# Breakout_Connector.net
KiCad netlist of a schematic drawn in Altium Designer
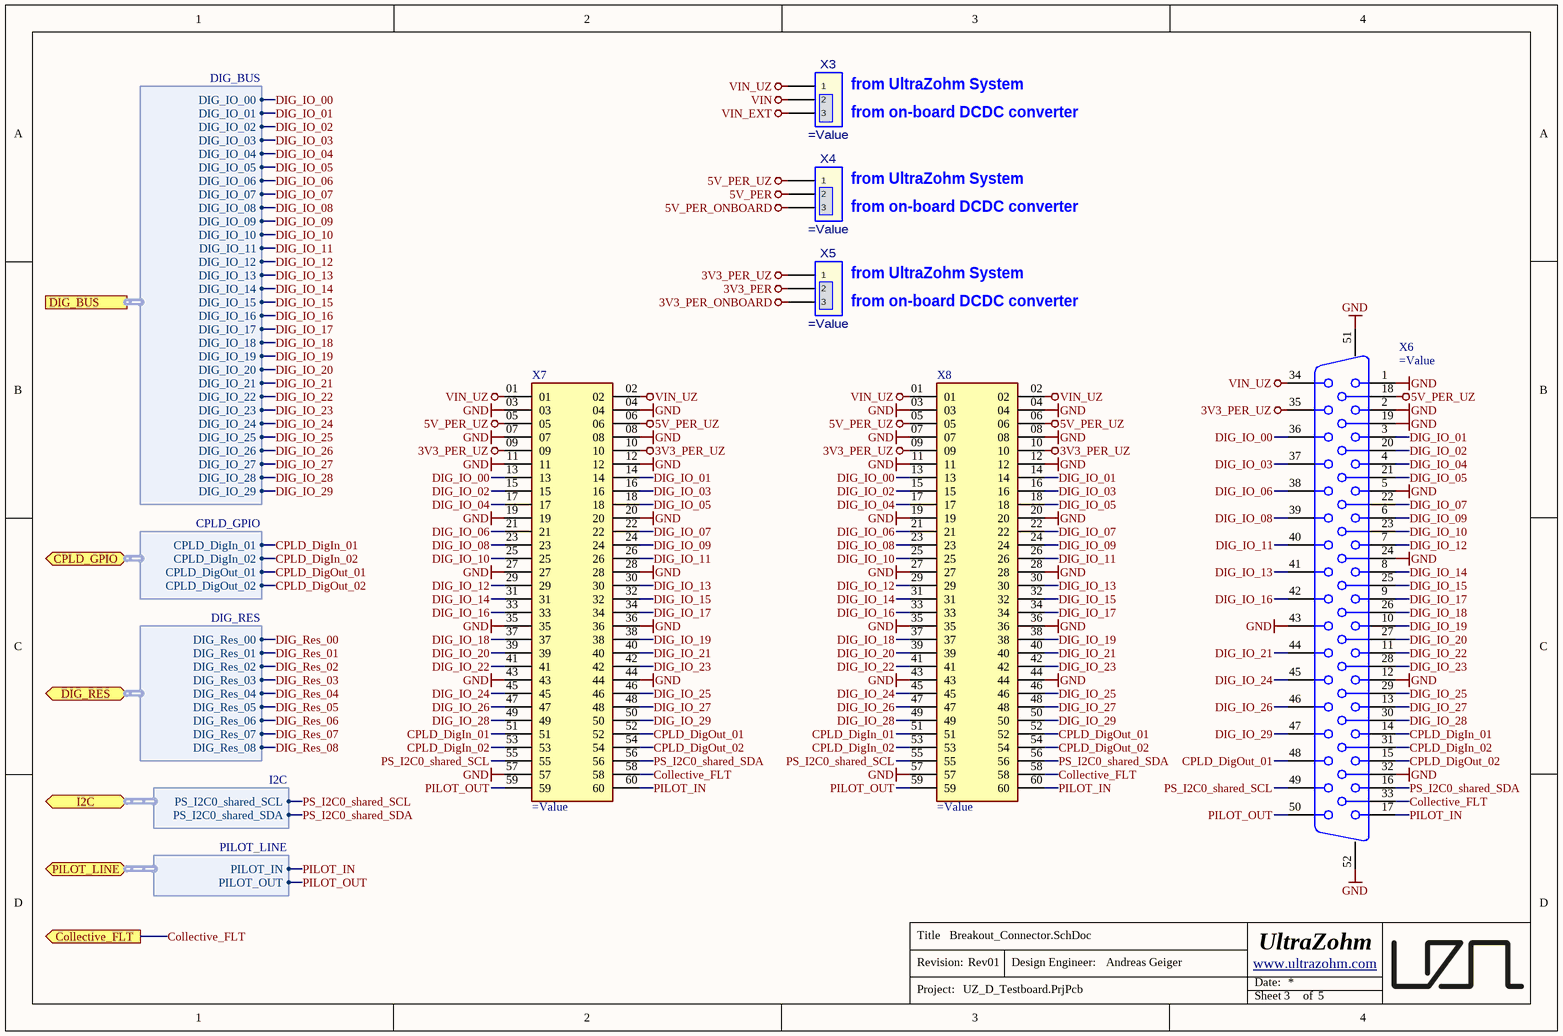
[diagram p0: Breakout_Connector.SchDoc]

(export (version "E")
  (design (tool "Eeschema 10.0.6"))
  (components
    (comp (ref "X3")
      (value "~")
      (footprint "TSW-103-XX-XXX-S")
      (description ".025[0.64] SQ. POST TERMINAL STRIP ASSEMBLY.")
      (fields
        (field (name "MANUFACTURER") "SAMTEC")
        (field (name "MPN") "TSW-103-07-F-S")
        (field (name "CREATED") "2020_11_26_AGeiger")
      )
      (libsource (lib "UZ_D_Testboard") (part "TSW-103-XX-XXX-S"))
    )
    (comp (ref "X4")
      (value "~")
      (footprint "TSW-103-XX-XXX-S")
      (description ".025[0.64] SQ. POST TERMINAL STRIP ASSEMBLY.")
      (fields
        (field (name "MANUFACTURER") "SAMTEC")
        (field (name "MPN") "TSW-103-07-F-S")
        (field (name "CREATED") "2020_11_26_AGeiger")
      )
      (libsource (lib "UZ_D_Testboard") (part "TSW-103-XX-XXX-S"))
    )
    (comp (ref "X5")
      (value "~")
      (footprint "TSW-103-XX-XXX-S")
      (description ".025[0.64] SQ. POST TERMINAL STRIP ASSEMBLY.")
      (fields
        (field (name "MANUFACTURER") "SAMTEC")
        (field (name "MPN") "TSW-103-07-F-S")
        (field (name "CREATED") "2020_11_26_AGeiger")
      )
      (libsource (lib "UZ_D_Testboard") (part "TSW-103-XX-XXX-S"))
    )
    (comp (ref "X6")
      (value "~")
      (footprint "dsub50_male_163A18339X")
      (description "D-SUB, male, right angle, 50pos, 9.4mm pitch")
      (fields
        (field (name "MF") "CONEC")
        (field (name "MPN") "163A18339X")
        (field (name "CREATED") "2021_03_25_AGeiger")
      )
      (libsource (lib "UZ_D_Testboard") (part "DSUB50_male"))
    )
    (comp (ref "X7")
      (value "~")
      (footprint "TSM-130-01-F-DV")
      (fields
        (field (name "MF") "Samtec")
        (field (name "MPN") "TSM-130-01-F-DV")
        (field (name "CREATED") "2021_03_23_AGeiger")
      )
      (libsource (lib "UZ_D_Testboard") (part "TSM-130-01-F-DV"))
    )
    (comp (ref "X8")
      (value "~")
      (footprint "HTSS-130-01-L-DV")
      (fields (field (name "MF") "SAMTEC") (field (name "MPN") "HTSS-130-01-L-DV"))
      (libsource (lib "UZ_D_Testboard") (part "HTSS-130-01-L-DV"))
    )
  )
  (nets
    (net (code "6") (name "/CPLD_DigIn_01") (class "Default")
      (node (ref "X6") (pin "14") (pinfunction "14_14") (pintype "passive"))
      (node (ref "X7") (pin "51") (pinfunction "51_51") (pintype "passive"))
      (node (ref "X8") (pin "51") (pinfunction "51_51") (pintype "passive"))
    )
    (net (code "7") (name "/CPLD_DigIn_02") (class "Default")
      (node (ref "X6") (pin "31") (pinfunction "31_31") (pintype "passive"))
      (node (ref "X7") (pin "53") (pinfunction "53_53") (pintype "passive"))
      (node (ref "X8") (pin "53") (pinfunction "53_53") (pintype "passive"))
    )
    (net (code "8") (name "/CPLD_DigOut_01") (class "Default")
      (node (ref "X6") (pin "48") (pinfunction "48_48") (pintype "passive"))
      (node (ref "X7") (pin "52") (pinfunction "52_52") (pintype "passive"))
      (node (ref "X8") (pin "52") (pinfunction "52_52") (pintype "passive"))
    )
    (net (code "9") (name "/CPLD_DigOut_02") (class "Default")
      (node (ref "X6") (pin "15") (pinfunction "15_15") (pintype "passive"))
      (node (ref "X7") (pin "54") (pinfunction "54_54") (pintype "passive"))
      (node (ref "X8") (pin "54") (pinfunction "54_54") (pintype "passive"))
    )
    (net (code "10") (name "/Collective_FLT") (class "Default")
      (node (ref "X6") (pin "33") (pinfunction "33_33") (pintype "passive"))
      (node (ref "X7") (pin "58") (pinfunction "58_58") (pintype "passive"))
      (node (ref "X8") (pin "58") (pinfunction "58_58") (pintype "passive"))
    )
    (net (code "11") (name "/DIG_IO_00") (class "Default")
      (node (ref "X6") (pin "36") (pinfunction "36_36") (pintype "passive"))
      (node (ref "X7") (pin "13") (pinfunction "13_13") (pintype "passive"))
      (node (ref "X8") (pin "13") (pinfunction "13_13") (pintype "passive"))
    )
    (net (code "12") (name "/DIG_IO_01") (class "Default")
      (node (ref "X6") (pin "3") (pinfunction "3_3") (pintype "passive"))
      (node (ref "X7") (pin "14") (pinfunction "14_14") (pintype "passive"))
      (node (ref "X8") (pin "14") (pinfunction "14_14") (pintype "passive"))
    )
    (net (code "13") (name "/DIG_IO_02") (class "Default")
      (node (ref "X6") (pin "20") (pinfunction "20_20") (pintype "passive"))
      (node (ref "X7") (pin "15") (pinfunction "15_15") (pintype "passive"))
      (node (ref "X8") (pin "15") (pinfunction "15_15") (pintype "passive"))
    )
    (net (code "14") (name "/DIG_IO_03") (class "Default")
      (node (ref "X6") (pin "37") (pinfunction "37_37") (pintype "passive"))
      (node (ref "X7") (pin "16") (pinfunction "16_16") (pintype "passive"))
      (node (ref "X8") (pin "16") (pinfunction "16_16") (pintype "passive"))
    )
    (net (code "15") (name "/DIG_IO_04") (class "Default")
      (node (ref "X6") (pin "4") (pinfunction "4_4") (pintype "passive"))
      (node (ref "X7") (pin "17") (pinfunction "17_17") (pintype "passive"))
      (node (ref "X8") (pin "17") (pinfunction "17_17") (pintype "passive"))
    )
    (net (code "16") (name "/DIG_IO_05") (class "Default")
      (node (ref "X6") (pin "21") (pinfunction "21_21") (pintype "passive"))
      (node (ref "X7") (pin "18") (pinfunction "18_18") (pintype "passive"))
      (node (ref "X8") (pin "18") (pinfunction "18_18") (pintype "passive"))
    )
    (net (code "17") (name "/DIG_IO_06") (class "Default")
      (node (ref "X6") (pin "38") (pinfunction "38_38") (pintype "passive"))
      (node (ref "X7") (pin "21") (pinfunction "21_21") (pintype "passive"))
      (node (ref "X8") (pin "21") (pinfunction "21_21") (pintype "passive"))
    )
    (net (code "18") (name "/DIG_IO_07") (class "Default")
      (node (ref "X6") (pin "22") (pinfunction "22_22") (pintype "passive"))
      (node (ref "X7") (pin "22") (pinfunction "22_22") (pintype "passive"))
      (node (ref "X8") (pin "22") (pinfunction "22_22") (pintype "passive"))
    )
    (net (code "19") (name "/DIG_IO_08") (class "Default")
      (node (ref "X6") (pin "39") (pinfunction "39_39") (pintype "passive"))
      (node (ref "X7") (pin "23") (pinfunction "23_23") (pintype "passive"))
      (node (ref "X8") (pin "23") (pinfunction "23_23") (pintype "passive"))
    )
    (net (code "20") (name "/DIG_IO_09") (class "Default")
      (node (ref "X6") (pin "6") (pinfunction "6_6") (pintype "passive"))
      (node (ref "X7") (pin "24") (pinfunction "24_24") (pintype "passive"))
      (node (ref "X8") (pin "24") (pinfunction "24_24") (pintype "passive"))
    )
    (net (code "21") (name "/DIG_IO_10") (class "Default")
      (node (ref "X6") (pin "23") (pinfunction "23_23") (pintype "passive"))
      (node (ref "X7") (pin "25") (pinfunction "25_25") (pintype "passive"))
      (node (ref "X8") (pin "25") (pinfunction "25_25") (pintype "passive"))
    )
    (net (code "22") (name "/DIG_IO_11") (class "Default")
      (node (ref "X6") (pin "40") (pinfunction "40_40") (pintype "passive"))
      (node (ref "X7") (pin "26") (pinfunction "26_26") (pintype "passive"))
      (node (ref "X8") (pin "26") (pinfunction "26_26") (pintype "passive"))
    )
    (net (code "23") (name "/DIG_IO_12") (class "Default")
      (node (ref "X6") (pin "7") (pinfunction "7_7") (pintype "passive"))
      (node (ref "X7") (pin "29") (pinfunction "29_29") (pintype "passive"))
      (node (ref "X8") (pin "29") (pinfunction "29_29") (pintype "passive"))
    )
    (net (code "24") (name "/DIG_IO_13") (class "Default")
      (node (ref "X6") (pin "41") (pinfunction "41_41") (pintype "passive"))
      (node (ref "X7") (pin "30") (pinfunction "30_30") (pintype "passive"))
      (node (ref "X8") (pin "30") (pinfunction "30_30") (pintype "passive"))
    )
    (net (code "25") (name "/DIG_IO_14") (class "Default")
      (node (ref "X6") (pin "8") (pinfunction "8_8") (pintype "passive"))
      (node (ref "X7") (pin "31") (pinfunction "31_31") (pintype "passive"))
      (node (ref "X8") (pin "31") (pinfunction "31_31") (pintype "passive"))
    )
    (net (code "26") (name "/DIG_IO_15") (class "Default")
      (node (ref "X6") (pin "25") (pinfunction "25_25") (pintype "passive"))
      (node (ref "X7") (pin "32") (pinfunction "32_32") (pintype "passive"))
      (node (ref "X8") (pin "32") (pinfunction "32_32") (pintype "passive"))
    )
    (net (code "27") (name "/DIG_IO_16") (class "Default")
      (node (ref "X6") (pin "42") (pinfunction "42_42") (pintype "passive"))
      (node (ref "X7") (pin "33") (pinfunction "33_33") (pintype "passive"))
      (node (ref "X8") (pin "33") (pinfunction "33_33") (pintype "passive"))
    )
    (net (code "28") (name "/DIG_IO_17") (class "Default")
      (node (ref "X6") (pin "9") (pinfunction "9_9") (pintype "passive"))
      (node (ref "X7") (pin "34") (pinfunction "34_34") (pintype "passive"))
      (node (ref "X8") (pin "34") (pinfunction "34_34") (pintype "passive"))
    )
    (net (code "29") (name "/DIG_IO_18") (class "Default")
      (node (ref "X6") (pin "26") (pinfunction "26_26") (pintype "passive"))
      (node (ref "X7") (pin "37") (pinfunction "37_37") (pintype "passive"))
      (node (ref "X8") (pin "37") (pinfunction "37_37") (pintype "passive"))
    )
    (net (code "30") (name "/DIG_IO_19") (class "Default")
      (node (ref "X6") (pin "10") (pinfunction "10_10") (pintype "passive"))
      (node (ref "X7") (pin "38") (pinfunction "38_38") (pintype "passive"))
      (node (ref "X8") (pin "38") (pinfunction "38_38") (pintype "passive"))
    )
    (net (code "31") (name "/DIG_IO_20") (class "Default")
      (node (ref "X6") (pin "27") (pinfunction "27_27") (pintype "passive"))
      (node (ref "X7") (pin "39") (pinfunction "39_39") (pintype "passive"))
      (node (ref "X8") (pin "39") (pinfunction "39_39") (pintype "passive"))
    )
    (net (code "32") (name "/DIG_IO_21") (class "Default")
      (node (ref "X6") (pin "44") (pinfunction "44_44") (pintype "passive"))
      (node (ref "X7") (pin "40") (pinfunction "40_40") (pintype "passive"))
      (node (ref "X8") (pin "40") (pinfunction "40_40") (pintype "passive"))
    )
    (net (code "33") (name "/DIG_IO_22") (class "Default")
      (node (ref "X6") (pin "11") (pinfunction "11_11") (pintype "passive"))
      (node (ref "X7") (pin "41") (pinfunction "41_41") (pintype "passive"))
      (node (ref "X8") (pin "41") (pinfunction "41_41") (pintype "passive"))
    )
    (net (code "34") (name "/DIG_IO_23") (class "Default")
      (node (ref "X6") (pin "28") (pinfunction "28_28") (pintype "passive"))
      (node (ref "X7") (pin "42") (pinfunction "42_42") (pintype "passive"))
      (node (ref "X8") (pin "42") (pinfunction "42_42") (pintype "passive"))
    )
    (net (code "35") (name "/DIG_IO_24") (class "Default")
      (node (ref "X6") (pin "45") (pinfunction "45_45") (pintype "passive"))
      (node (ref "X7") (pin "45") (pinfunction "45_45") (pintype "passive"))
      (node (ref "X8") (pin "45") (pinfunction "45_45") (pintype "passive"))
    )
    (net (code "36") (name "/DIG_IO_25") (class "Default")
      (node (ref "X6") (pin "29") (pinfunction "29_29") (pintype "passive"))
      (node (ref "X7") (pin "46") (pinfunction "46_46") (pintype "passive"))
      (node (ref "X8") (pin "46") (pinfunction "46_46") (pintype "passive"))
    )
    (net (code "37") (name "/DIG_IO_26") (class "Default")
      (node (ref "X6") (pin "46") (pinfunction "46_46") (pintype "passive"))
      (node (ref "X7") (pin "47") (pinfunction "47_47") (pintype "passive"))
      (node (ref "X8") (pin "47") (pinfunction "47_47") (pintype "passive"))
    )
    (net (code "38") (name "/DIG_IO_27") (class "Default")
      (node (ref "X6") (pin "13") (pinfunction "13_13") (pintype "passive"))
      (node (ref "X7") (pin "48") (pinfunction "48_48") (pintype "passive"))
      (node (ref "X8") (pin "48") (pinfunction "48_48") (pintype "passive"))
    )
    (net (code "39") (name "/DIG_IO_28") (class "Default")
      (node (ref "X6") (pin "30") (pinfunction "30_30") (pintype "passive"))
      (node (ref "X7") (pin "49") (pinfunction "49_49") (pintype "passive"))
      (node (ref "X8") (pin "49") (pinfunction "49_49") (pintype "passive"))
    )
    (net (code "40") (name "/DIG_IO_29") (class "Default")
      (node (ref "X6") (pin "47") (pinfunction "47_47") (pintype "passive"))
      (node (ref "X7") (pin "50") (pinfunction "50_50") (pintype "passive"))
      (node (ref "X8") (pin "50") (pinfunction "50_50") (pintype "passive"))
    )
    (net (code "50") (name "/PILOT_IN") (class "Default")
      (node (ref "X6") (pin "17") (pinfunction "17_17") (pintype "passive"))
      (node (ref "X7") (pin "60") (pinfunction "60_60") (pintype "passive"))
      (node (ref "X8") (pin "60") (pinfunction "60_60") (pintype "passive"))
    )
    (net (code "51") (name "/PILOT_OUT") (class "Default")
      (node (ref "X6") (pin "50") (pinfunction "50_50") (pintype "passive"))
      (node (ref "X7") (pin "59") (pinfunction "59_59") (pintype "passive"))
      (node (ref "X8") (pin "59") (pinfunction "59_59") (pintype "passive"))
    )
    (net (code "52") (name "/PS_I2C0_shared_SCL") (class "Default")
      (node (ref "X6") (pin "49") (pinfunction "49_49") (pintype "passive"))
      (node (ref "X7") (pin "55") (pinfunction "55_55") (pintype "passive"))
      (node (ref "X8") (pin "55") (pinfunction "55_55") (pintype "passive"))
    )
    (net (code "53") (name "/PS_I2C0_shared_SDA") (class "Default")
      (node (ref "X6") (pin "16") (pinfunction "16_16") (pintype "passive"))
      (node (ref "X7") (pin "56") (pinfunction "56_56") (pintype "passive"))
      (node (ref "X8") (pin "56") (pinfunction "56_56") (pintype "passive"))
    )
    (net (code "59") (name "3V3_PER") (class "Default")
      (node (ref "X5") (pin "2") (pinfunction "2_2") (pintype "passive"))
    )
    (net (code "60") (name "3V3_PER_ONBOARD") (class "Default")
      (node (ref "X5") (pin "3") (pinfunction "3_3") (pintype "passive"))
    )
    (net (code "61") (name "3V3_PER_UZ") (class "Default")
      (node (ref "X5") (pin "1") (pinfunction "1_1") (pintype "passive"))
      (node (ref "X6") (pin "35") (pinfunction "35_35") (pintype "passive"))
      (node (ref "X7") (pin "09") (pinfunction "09_09") (pintype "passive"))
      (node (ref "X7") (pin "10") (pinfunction "10_10") (pintype "passive"))
      (node (ref "X8") (pin "09") (pinfunction "09_09") (pintype "passive"))
      (node (ref "X8") (pin "10") (pinfunction "10_10") (pintype "passive"))
    )
    (net (code "62") (name "5V_PER") (class "Default")
      (node (ref "X4") (pin "2") (pinfunction "2_2") (pintype "passive"))
    )
    (net (code "63") (name "5V_PER_ONBOARD") (class "Default")
      (node (ref "X4") (pin "3") (pinfunction "3_3") (pintype "passive"))
    )
    (net (code "64") (name "5V_PER_UZ") (class "Default")
      (node (ref "X4") (pin "1") (pinfunction "1_1") (pintype "passive"))
      (node (ref "X6") (pin "18") (pinfunction "18_18") (pintype "passive"))
      (node (ref "X7") (pin "05") (pinfunction "05_05") (pintype "passive"))
      (node (ref "X7") (pin "06") (pinfunction "06_06") (pintype "passive"))
      (node (ref "X8") (pin "05") (pinfunction "05_05") (pintype "passive"))
      (node (ref "X8") (pin "06") (pinfunction "06_06") (pintype "passive"))
    )
    (net (code "65") (name "GND") (class "Default")
      (node (ref "X6") (pin "1") (pinfunction "1_1") (pintype "passive"))
      (node (ref "X6") (pin "12") (pinfunction "12_12") (pintype "passive"))
      (node (ref "X6") (pin "19") (pinfunction "19_19") (pintype "passive"))
      (node (ref "X6") (pin "2") (pinfunction "2_2") (pintype "passive"))
      (node (ref "X6") (pin "24") (pinfunction "24_24") (pintype "passive"))
      (node (ref "X6") (pin "32") (pinfunction "32_32") (pintype "passive"))
      (node (ref "X6") (pin "43") (pinfunction "43_43") (pintype "passive"))
      (node (ref "X6") (pin "5") (pinfunction "5_5") (pintype "passive"))
      (node (ref "X6") (pin "51") (pinfunction "51_51") (pintype "passive"))
      (node (ref "X6") (pin "52") (pinfunction "52_52") (pintype "passive"))
      (node (ref "X7") (pin "03") (pinfunction "03_03") (pintype "passive"))
      (node (ref "X7") (pin "04") (pinfunction "04_04") (pintype "passive"))
      (node (ref "X7") (pin "07") (pinfunction "07_07") (pintype "passive"))
      (node (ref "X7") (pin "08") (pinfunction "08_08") (pintype "passive"))
      (node (ref "X7") (pin "11") (pinfunction "11_11") (pintype "passive"))
      (node (ref "X7") (pin "12") (pinfunction "12_12") (pintype "passive"))
      (node (ref "X7") (pin "19") (pinfunction "19_19") (pintype "passive"))
      (node (ref "X7") (pin "20") (pinfunction "20_20") (pintype "passive"))
      (node (ref "X7") (pin "27") (pinfunction "27_27") (pintype "passive"))
      (node (ref "X7") (pin "28") (pinfunction "28_28") (pintype "passive"))
      (node (ref "X7") (pin "35") (pinfunction "35_35") (pintype "passive"))
      (node (ref "X7") (pin "36") (pinfunction "36_36") (pintype "passive"))
      (node (ref "X7") (pin "43") (pinfunction "43_43") (pintype "passive"))
      (node (ref "X7") (pin "44") (pinfunction "44_44") (pintype "passive"))
      (node (ref "X7") (pin "57") (pinfunction "57_57") (pintype "passive"))
      (node (ref "X8") (pin "03") (pinfunction "03_03") (pintype "passive"))
      (node (ref "X8") (pin "04") (pinfunction "04_04") (pintype "passive"))
      (node (ref "X8") (pin "07") (pinfunction "07_07") (pintype "passive"))
      (node (ref "X8") (pin "08") (pinfunction "08_08") (pintype "passive"))
      (node (ref "X8") (pin "11") (pinfunction "11_11") (pintype "passive"))
      (node (ref "X8") (pin "12") (pinfunction "12_12") (pintype "passive"))
      (node (ref "X8") (pin "19") (pinfunction "19_19") (pintype "passive"))
      (node (ref "X8") (pin "20") (pinfunction "20_20") (pintype "passive"))
      (node (ref "X8") (pin "27") (pinfunction "27_27") (pintype "passive"))
      (node (ref "X8") (pin "28") (pinfunction "28_28") (pintype "passive"))
      (node (ref "X8") (pin "35") (pinfunction "35_35") (pintype "passive"))
      (node (ref "X8") (pin "36") (pinfunction "36_36") (pintype "passive"))
      (node (ref "X8") (pin "43") (pinfunction "43_43") (pintype "passive"))
      (node (ref "X8") (pin "44") (pinfunction "44_44") (pintype "passive"))
      (node (ref "X8") (pin "57") (pinfunction "57_57") (pintype "passive"))
    )
    (net (code "66") (name "VIN") (class "Default")
      (node (ref "X3") (pin "2") (pinfunction "2_2") (pintype "passive"))
    )
    (net (code "67") (name "VIN_EXT") (class "Default")
      (node (ref "X3") (pin "3") (pinfunction "3_3") (pintype "passive"))
    )
    (net (code "68") (name "VIN_UZ") (class "Default")
      (node (ref "X3") (pin "1") (pinfunction "1_1") (pintype "passive"))
      (node (ref "X6") (pin "34") (pinfunction "34_34") (pintype "passive"))
      (node (ref "X7") (pin "01") (pinfunction "01_01") (pintype "passive"))
      (node (ref "X7") (pin "02") (pinfunction "02_02") (pintype "passive"))
      (node (ref "X8") (pin "01") (pinfunction "01_01") (pintype "passive"))
      (node (ref "X8") (pin "02") (pinfunction "02_02") (pintype "passive"))
    )
  )
)
